# dcdc.net
KiCad netlist of a schematic drawn in Altium Designer
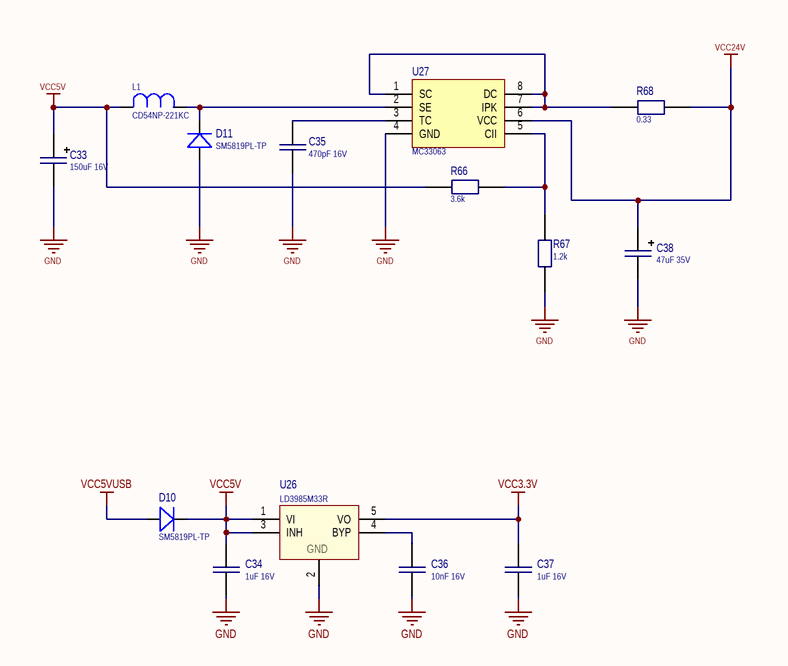
[diagram p0: dcdc.schdoc]

(export (version "E")
  (design (tool "Eeschema 10.0.6"))
  (components
    (comp (ref "C33")
      (value "150uF 16V")
      (footprint "TANTAL_TYPE_D")
      (description "Tantal Capacitor")
      (fields
        (field (name "PART NUMBER") "T491D157K016AT")
        (field (name "ALTERNATIVE PART") "TAJD157K016RNJ")
      )
      (libsource (lib "capacitors") (part "TANTAL_CAP"))
    )
    (comp (ref "C34")
      (value "1uF 16V")
      (footprint "C_0603")
      (description "Capacitor")
      (fields (field (name "PART NUMBER") "CC0603KRX7R7BB105"))
      (libsource (lib "capacitors") (part "C0603"))
    )
    (comp (ref "C35")
      (value "470pF 16V")
      (footprint "C_0603")
      (description "Capacitor")
      (fields (field (name "PART NUMBER") "CC0603KRX7R9BB471"))
      (libsource (lib "capacitors") (part "C0603"))
    )
    (comp (ref "C36")
      (value "10nF 16V")
      (footprint "C_0603")
      (description "Capacitor")
      (fields (field (name "PART NUMBER") "CC0603JRX7R7BB103"))
      (libsource (lib "AX_Altium_v2.3") (part "C0603"))
    )
    (comp (ref "C37")
      (value "1uF 16V")
      (footprint "C_0603")
      (description "Capacitor")
      (fields (field (name "PART NUMBER") "CC0603KRX7R7BB105"))
      (libsource (lib "capacitors") (part "C0603"))
    )
    (comp (ref "C38")
      (value "47uF 35V")
      (footprint "TANTAL_TYPE_X")
      (description "Tantal Capacitor")
      (fields (field (name "PART NUMBER") "T491X476K035AT"))
      (libsource (lib "capacitors") (part "TANTAL_CAP"))
    )
    (comp (ref "D10")
      (value "SM5819PL-TP")
      (footprint "SOD-123")
      (description "Diode")
      (libsource (lib "AX_Altium_v2.3") (part "D_SOD123"))
    )
    (comp (ref "D11")
      (value "SM5819PL-TP")
      (footprint "SOD-123")
      (description "Diode")
      (libsource (lib "AX_Altium_v2.3") (part "D_SOD123"))
    )
    (comp (ref "L1")
      (value "CD54NP-221KC")
      (footprint "CD54NP")
      (description "Inductor")
      (fields (field (name "ALTERNATIVE PART") "SM5845-221MT"))
      (libsource (lib "AX_Altium_v2.3") (part "L_CD54NP"))
    )
    (comp (ref "R66")
      (value "3.6k")
      (footprint "R_0603")
      (description "Resistor")
      (fields (field (name "PART NUMBER") "RC0603FR-073K6L"))
      (libsource (lib "resistors") (part "RES_SMD"))
    )
    (comp (ref "R67")
      (value "1.2k")
      (footprint "R_0603")
      (description "Resistor")
      (fields (field (name "PART NUMBER") "RC0603FR-071K2L"))
      (libsource (lib "resistors") (part "RES_SMD"))
    )
    (comp (ref "R68")
      (value "0.33")
      (footprint "R_1206")
      (description "Resistor")
      (fields (field (name "PART NUMBER") "RL1206FR-070R33L"))
      (libsource (lib "resistors") (part "RES_SMD"))
    )
    (comp (ref "U26")
      (value "LD3985M33R")
      (footprint "AX_Altium_v2.3:SOT23-5")
      (description "Ultra low drop and low noise BiCMOS voltage regulators")
      (libsource (lib "dcdc_ldo_ref") (part "LD3985M33R"))
    )
    (comp (ref "U27")
      (value "MC33063")
      (footprint "SO-8")
      (description "Step-up/down IC")
      (fields (field (name "PART NUMBER") "MC33063AP"))
      (libsource (lib "dcdc_ldo_ref") (part "MC33063"))
    )
  )
  (nets
    (net (code "1") (name "GND") (class "Default")
      (node (ref "C33") (pin "2") (pinfunction "2_2") (pintype "passive"))
      (node (ref "C34") (pin "1") (pinfunction "1_1") (pintype "passive"))
      (node (ref "C35") (pin "1") (pinfunction "1_1") (pintype "passive"))
      (node (ref "C36") (pin "1") (pinfunction "1_1") (pintype "passive"))
      (node (ref "C37") (pin "1") (pinfunction "1_1") (pintype "passive"))
      (node (ref "C38") (pin "2") (pinfunction "2_2") (pintype "passive"))
      (node (ref "D11") (pin "1") (pinfunction "A_1") (pintype "passive"))
      (node (ref "R67") (pin "1") (pinfunction "1_1") (pintype "passive"))
      (node (ref "U26") (pin "2") (pinfunction "GND_2") (pintype "passive"))
      (node (ref "U27") (pin "4") (pinfunction "GND_4") (pintype "passive"))
    )
    (net (code "2") (name "Net-(D11-K)") (class "Default")
      (node (ref "D11") (pin "2") (pinfunction "K_2") (pintype "passive"))
      (node (ref "L1") (pin "1") (pintype "passive"))
      (node (ref "U27") (pin "2") (pinfunction "SE_2") (pintype "passive"))
    )
    (net (code "3") (name "Net-(U26-BYP)") (class "Default")
      (node (ref "C36") (pin "2") (pinfunction "2_2") (pintype "passive"))
      (node (ref "U26") (pin "4") (pinfunction "BYP_4") (pintype "passive"))
    )
    (net (code "4") (name "Net-(U27-CII)") (class "Default")
      (node (ref "R66") (pin "2") (pinfunction "2_2") (pintype "passive"))
      (node (ref "R67") (pin "2") (pinfunction "2_2") (pintype "passive"))
      (node (ref "U27") (pin "5") (pinfunction "CII_5") (pintype "passive"))
    )
    (net (code "5") (name "Net-(U27-DC)") (class "Default")
      (node (ref "R68") (pin "2") (pinfunction "2_2") (pintype "passive"))
      (node (ref "U27") (pin "1") (pinfunction "SC_1") (pintype "passive"))
      (node (ref "U27") (pin "7") (pinfunction "IPK_7") (pintype "passive"))
      (node (ref "U27") (pin "8") (pinfunction "DC_8") (pintype "passive"))
    )
    (net (code "6") (name "Net-(U27-TC)") (class "Default")
      (node (ref "C35") (pin "2") (pinfunction "2_2") (pintype "passive"))
      (node (ref "U27") (pin "3") (pinfunction "TC_3") (pintype "passive"))
    )
    (net (code "7") (name "VCC3.3V") (class "Default")
      (node (ref "C37") (pin "2") (pinfunction "2_2") (pintype "passive"))
      (node (ref "U26") (pin "5") (pinfunction "VO_5") (pintype "passive"))
    )
    (net (code "8") (name "VCC5V") (class "Default")
      (node (ref "C33") (pin "1") (pinfunction "1_1") (pintype "passive"))
      (node (ref "C34") (pin "2") (pinfunction "2_2") (pintype "passive"))
      (node (ref "D10") (pin "2") (pinfunction "K_2") (pintype "passive"))
      (node (ref "L1") (pin "2") (pintype "passive"))
      (node (ref "R66") (pin "1") (pinfunction "1_1") (pintype "passive"))
      (node (ref "U26") (pin "1") (pinfunction "VI_1") (pintype "passive"))
      (node (ref "U26") (pin "3") (pinfunction "INH_3") (pintype "passive"))
    )
    (net (code "9") (name "VCC5VUSB") (class "Default")
      (node (ref "D10") (pin "1") (pinfunction "A_1") (pintype "passive"))
    )
    (net (code "10") (name "VCC24V") (class "Default")
      (node (ref "C38") (pin "1") (pinfunction "1_1") (pintype "passive"))
      (node (ref "R68") (pin "1") (pinfunction "1_1") (pintype "passive"))
      (node (ref "U27") (pin "6") (pinfunction "VCC_6") (pintype "passive"))
    )
  )
)
